# FLD_Logic_2.net
KiCad netlist of a schematic drawn in EAGLE
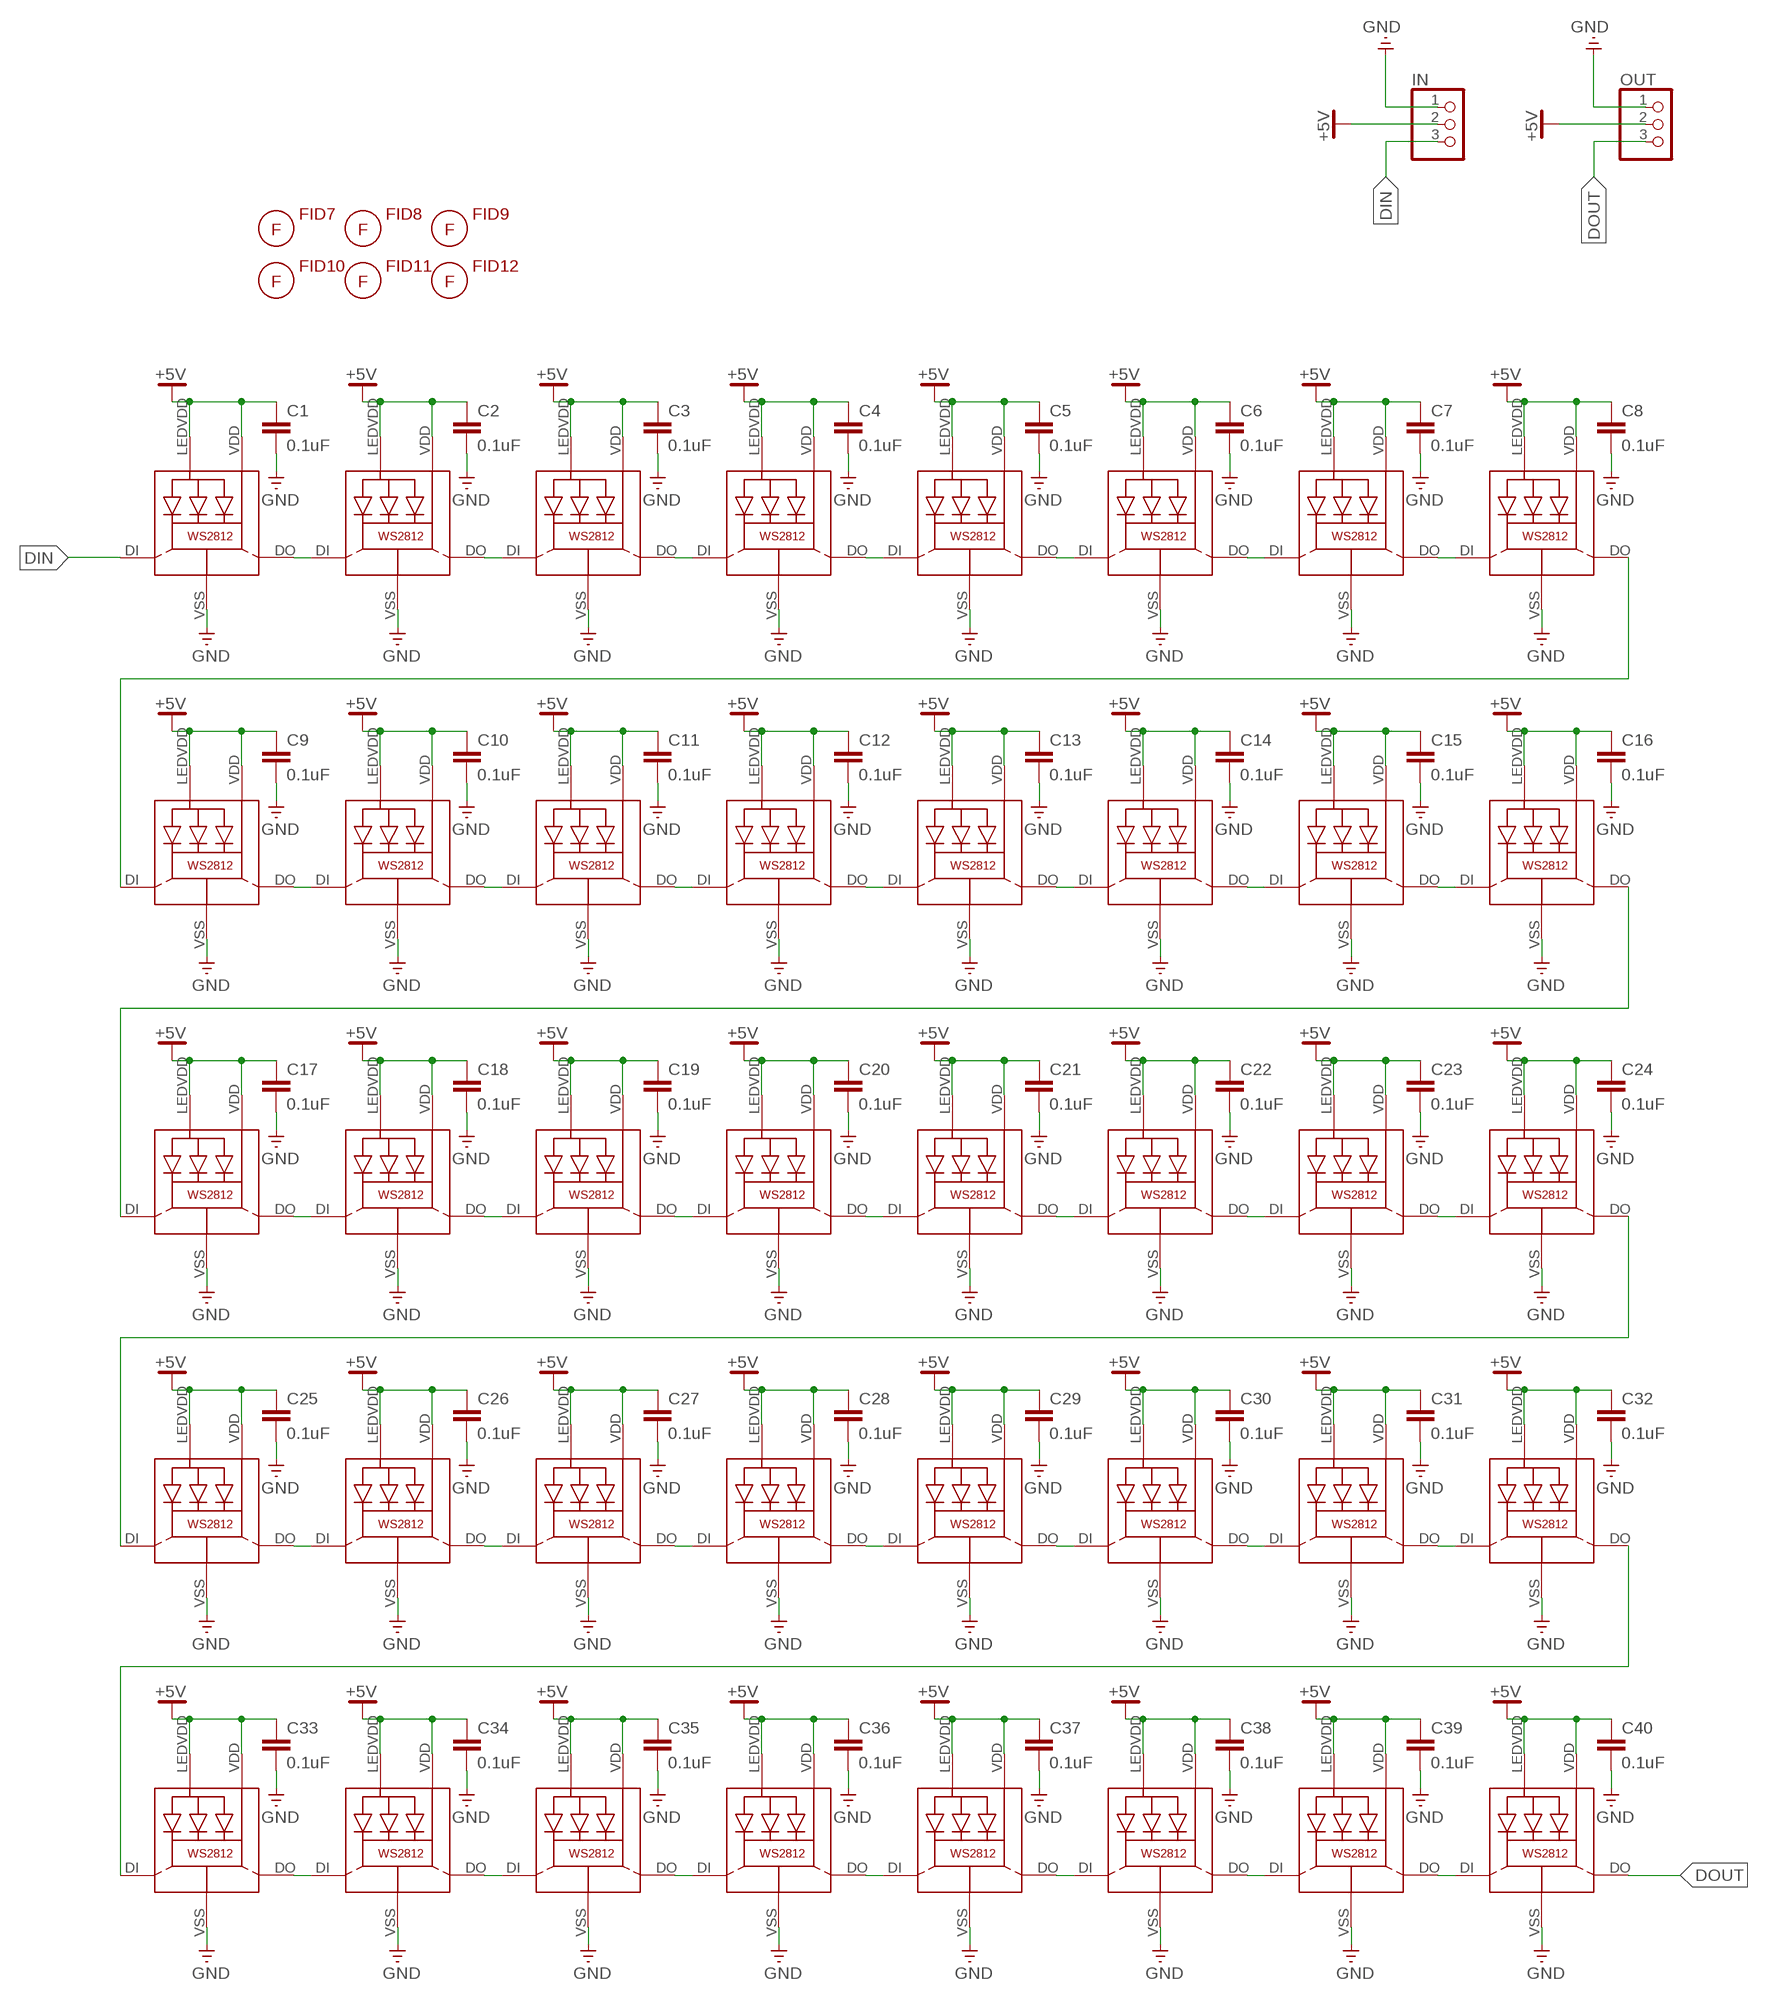
[diagram p0: schematic, sheet 1]

(export (version "E")
  (design (tool "Eeschema 10.0.6"))
  (components
    (comp (ref "C1")
      (value "0.1uF")
      (footprint "eagle-import:0805")
      (libsource (lib "eagle-import") (part "CAP0805"))
    )
    (comp (ref "C2")
      (value "0.1uF")
      (footprint "eagle-import:0805")
      (libsource (lib "eagle-import") (part "CAP0805"))
    )
    (comp (ref "C3")
      (value "0.1uF")
      (footprint "eagle-import:0805")
      (libsource (lib "eagle-import") (part "CAP0805"))
    )
    (comp (ref "C4")
      (value "0.1uF")
      (footprint "eagle-import:0805")
      (libsource (lib "eagle-import") (part "CAP0805"))
    )
    (comp (ref "C5")
      (value "0.1uF")
      (footprint "eagle-import:0805")
      (libsource (lib "eagle-import") (part "CAP0805"))
    )
    (comp (ref "C6")
      (value "0.1uF")
      (footprint "eagle-import:0805")
      (libsource (lib "eagle-import") (part "CAP0805"))
    )
    (comp (ref "C7")
      (value "0.1uF")
      (footprint "eagle-import:0805")
      (libsource (lib "eagle-import") (part "CAP0805"))
    )
    (comp (ref "C8")
      (value "0.1uF")
      (footprint "eagle-import:0805")
      (libsource (lib "eagle-import") (part "CAP0805"))
    )
    (comp (ref "C9")
      (value "0.1uF")
      (footprint "eagle-import:0805")
      (libsource (lib "eagle-import") (part "CAP0805"))
    )
    (comp (ref "C10")
      (value "0.1uF")
      (footprint "eagle-import:0805")
      (libsource (lib "eagle-import") (part "CAP0805"))
    )
    (comp (ref "C11")
      (value "0.1uF")
      (footprint "eagle-import:0805")
      (libsource (lib "eagle-import") (part "CAP0805"))
    )
    (comp (ref "C12")
      (value "0.1uF")
      (footprint "eagle-import:0805")
      (libsource (lib "eagle-import") (part "CAP0805"))
    )
    (comp (ref "C13")
      (value "0.1uF")
      (footprint "eagle-import:0805")
      (libsource (lib "eagle-import") (part "CAP0805"))
    )
    (comp (ref "C14")
      (value "0.1uF")
      (footprint "eagle-import:0805")
      (libsource (lib "eagle-import") (part "CAP0805"))
    )
    (comp (ref "C15")
      (value "0.1uF")
      (footprint "eagle-import:0805")
      (libsource (lib "eagle-import") (part "CAP0805"))
    )
    (comp (ref "C16")
      (value "0.1uF")
      (footprint "eagle-import:0805")
      (libsource (lib "eagle-import") (part "CAP0805"))
    )
    (comp (ref "C17")
      (value "0.1uF")
      (footprint "eagle-import:0805")
      (libsource (lib "eagle-import") (part "CAP0805"))
    )
    (comp (ref "C18")
      (value "0.1uF")
      (footprint "eagle-import:0805")
      (libsource (lib "eagle-import") (part "CAP0805"))
    )
    (comp (ref "C19")
      (value "0.1uF")
      (footprint "eagle-import:0805")
      (libsource (lib "eagle-import") (part "CAP0805"))
    )
    (comp (ref "C20")
      (value "0.1uF")
      (footprint "eagle-import:0805")
      (libsource (lib "eagle-import") (part "CAP0805"))
    )
    (comp (ref "C21")
      (value "0.1uF")
      (footprint "eagle-import:0805")
      (libsource (lib "eagle-import") (part "CAP0805"))
    )
    (comp (ref "C22")
      (value "0.1uF")
      (footprint "eagle-import:0805")
      (libsource (lib "eagle-import") (part "CAP0805"))
    )
    (comp (ref "C23")
      (value "0.1uF")
      (footprint "eagle-import:0805")
      (libsource (lib "eagle-import") (part "CAP0805"))
    )
    (comp (ref "C24")
      (value "0.1uF")
      (footprint "eagle-import:0805")
      (libsource (lib "eagle-import") (part "CAP0805"))
    )
    (comp (ref "C25")
      (value "0.1uF")
      (footprint "eagle-import:0805")
      (libsource (lib "eagle-import") (part "CAP0805"))
    )
    (comp (ref "C26")
      (value "0.1uF")
      (footprint "eagle-import:0805")
      (libsource (lib "eagle-import") (part "CAP0805"))
    )
    (comp (ref "C27")
      (value "0.1uF")
      (footprint "eagle-import:0805")
      (libsource (lib "eagle-import") (part "CAP0805"))
    )
    (comp (ref "C28")
      (value "0.1uF")
      (footprint "eagle-import:0805")
      (libsource (lib "eagle-import") (part "CAP0805"))
    )
    (comp (ref "C29")
      (value "0.1uF")
      (footprint "eagle-import:0805")
      (libsource (lib "eagle-import") (part "CAP0805"))
    )
    (comp (ref "C30")
      (value "0.1uF")
      (footprint "eagle-import:0805")
      (libsource (lib "eagle-import") (part "CAP0805"))
    )
    (comp (ref "C31")
      (value "0.1uF")
      (footprint "eagle-import:0805")
      (libsource (lib "eagle-import") (part "CAP0805"))
    )
    (comp (ref "C32")
      (value "0.1uF")
      (footprint "eagle-import:0805")
      (libsource (lib "eagle-import") (part "CAP0805"))
    )
    (comp (ref "C33")
      (value "0.1uF")
      (footprint "eagle-import:0805")
      (libsource (lib "eagle-import") (part "CAP0805"))
    )
    (comp (ref "C34")
      (value "0.1uF")
      (footprint "eagle-import:0805")
      (libsource (lib "eagle-import") (part "CAP0805"))
    )
    (comp (ref "C35")
      (value "0.1uF")
      (footprint "eagle-import:0805")
      (libsource (lib "eagle-import") (part "CAP0805"))
    )
    (comp (ref "C36")
      (value "0.1uF")
      (footprint "eagle-import:0805")
      (libsource (lib "eagle-import") (part "CAP0805"))
    )
    (comp (ref "C37")
      (value "0.1uF")
      (footprint "eagle-import:0805")
      (libsource (lib "eagle-import") (part "CAP0805"))
    )
    (comp (ref "C38")
      (value "0.1uF")
      (footprint "eagle-import:0805")
      (libsource (lib "eagle-import") (part "CAP0805"))
    )
    (comp (ref "C39")
      (value "0.1uF")
      (footprint "eagle-import:0805")
      (libsource (lib "eagle-import") (part "CAP0805"))
    )
    (comp (ref "C40")
      (value "0.1uF")
      (footprint "eagle-import:0805")
      (libsource (lib "eagle-import") (part "CAP0805"))
    )
    (comp (ref "FID7")
      (value "FIDUCIAL")
      (footprint "eagle-import:FIDUCIAL_G15")
      (libsource (lib "eagle-import") (part "FIDUCIAL"))
    )
    (comp (ref "FID8")
      (value "FIDUCIAL")
      (footprint "eagle-import:FIDUCIAL_G15")
      (libsource (lib "eagle-import") (part "FIDUCIAL"))
    )
    (comp (ref "FID9")
      (value "FIDUCIAL")
      (footprint "eagle-import:FIDUCIAL_G15")
      (libsource (lib "eagle-import") (part "FIDUCIAL"))
    )
    (comp (ref "FID10")
      (value "FIDUCIAL")
      (footprint "eagle-import:FIDUCIAL_G15")
      (libsource (lib "eagle-import") (part "FIDUCIAL"))
    )
    (comp (ref "FID11")
      (value "FIDUCIAL")
      (footprint "eagle-import:FIDUCIAL_G15")
      (libsource (lib "eagle-import") (part "FIDUCIAL"))
    )
    (comp (ref "FID12")
      (value "FIDUCIAL")
      (footprint "eagle-import:FIDUCIAL_G15")
      (libsource (lib "eagle-import") (part "FIDUCIAL"))
    )
    (comp (ref "IN")
      (value "PINHD-1X3")
      (footprint "eagle-import:1X03")
      (libsource (lib "eagle-import") (part "PINHD-1X3"))
    )
    (comp (ref "LED1")
      (value "WS2812")
      (footprint "eagle-import:WS2812")
      (libsource (lib "eagle-import") (part "WS2812"))
    )
    (comp (ref "LED2")
      (value "WS2812")
      (footprint "eagle-import:WS2812")
      (libsource (lib "eagle-import") (part "WS2812"))
    )
    (comp (ref "LED3")
      (value "WS2812")
      (footprint "eagle-import:WS2812")
      (libsource (lib "eagle-import") (part "WS2812"))
    )
    (comp (ref "LED4")
      (value "WS2812")
      (footprint "eagle-import:WS2812")
      (libsource (lib "eagle-import") (part "WS2812"))
    )
    (comp (ref "LED5")
      (value "WS2812")
      (footprint "eagle-import:WS2812")
      (libsource (lib "eagle-import") (part "WS2812"))
    )
    (comp (ref "LED6")
      (value "WS2812")
      (footprint "eagle-import:WS2812")
      (libsource (lib "eagle-import") (part "WS2812"))
    )
    (comp (ref "LED7")
      (value "WS2812")
      (footprint "eagle-import:WS2812")
      (libsource (lib "eagle-import") (part "WS2812"))
    )
    (comp (ref "LED8")
      (value "WS2812")
      (footprint "eagle-import:WS2812")
      (libsource (lib "eagle-import") (part "WS2812"))
    )
    (comp (ref "LED9")
      (value "WS2812")
      (footprint "eagle-import:WS2812")
      (libsource (lib "eagle-import") (part "WS2812"))
    )
    (comp (ref "LED10")
      (value "WS2812")
      (footprint "eagle-import:WS2812")
      (libsource (lib "eagle-import") (part "WS2812"))
    )
    (comp (ref "LED11")
      (value "WS2812")
      (footprint "eagle-import:WS2812")
      (libsource (lib "eagle-import") (part "WS2812"))
    )
    (comp (ref "LED12")
      (value "WS2812")
      (footprint "eagle-import:WS2812")
      (libsource (lib "eagle-import") (part "WS2812"))
    )
    (comp (ref "LED13")
      (value "WS2812")
      (footprint "eagle-import:WS2812")
      (libsource (lib "eagle-import") (part "WS2812"))
    )
    (comp (ref "LED14")
      (value "WS2812")
      (footprint "eagle-import:WS2812")
      (libsource (lib "eagle-import") (part "WS2812"))
    )
    (comp (ref "LED15")
      (value "WS2812")
      (footprint "eagle-import:WS2812")
      (libsource (lib "eagle-import") (part "WS2812"))
    )
    (comp (ref "LED16")
      (value "WS2812")
      (footprint "eagle-import:WS2812")
      (libsource (lib "eagle-import") (part "WS2812"))
    )
    (comp (ref "LED17")
      (value "WS2812")
      (footprint "eagle-import:WS2812")
      (libsource (lib "eagle-import") (part "WS2812"))
    )
    (comp (ref "LED18")
      (value "WS2812")
      (footprint "eagle-import:WS2812")
      (libsource (lib "eagle-import") (part "WS2812"))
    )
    (comp (ref "LED19")
      (value "WS2812")
      (footprint "eagle-import:WS2812")
      (libsource (lib "eagle-import") (part "WS2812"))
    )
    (comp (ref "LED20")
      (value "WS2812")
      (footprint "eagle-import:WS2812")
      (libsource (lib "eagle-import") (part "WS2812"))
    )
    (comp (ref "LED21")
      (value "WS2812")
      (footprint "eagle-import:WS2812")
      (libsource (lib "eagle-import") (part "WS2812"))
    )
    (comp (ref "LED22")
      (value "WS2812")
      (footprint "eagle-import:WS2812")
      (libsource (lib "eagle-import") (part "WS2812"))
    )
    (comp (ref "LED23")
      (value "WS2812")
      (footprint "eagle-import:WS2812")
      (libsource (lib "eagle-import") (part "WS2812"))
    )
    (comp (ref "LED24")
      (value "WS2812")
      (footprint "eagle-import:WS2812")
      (libsource (lib "eagle-import") (part "WS2812"))
    )
    (comp (ref "LED25")
      (value "WS2812")
      (footprint "eagle-import:WS2812")
      (libsource (lib "eagle-import") (part "WS2812"))
    )
    (comp (ref "LED26")
      (value "WS2812")
      (footprint "eagle-import:WS2812")
      (libsource (lib "eagle-import") (part "WS2812"))
    )
    (comp (ref "LED27")
      (value "WS2812")
      (footprint "eagle-import:WS2812")
      (libsource (lib "eagle-import") (part "WS2812"))
    )
    (comp (ref "LED28")
      (value "WS2812")
      (footprint "eagle-import:WS2812")
      (libsource (lib "eagle-import") (part "WS2812"))
    )
    (comp (ref "LED29")
      (value "WS2812")
      (footprint "eagle-import:WS2812")
      (libsource (lib "eagle-import") (part "WS2812"))
    )
    (comp (ref "LED30")
      (value "WS2812")
      (footprint "eagle-import:WS2812")
      (libsource (lib "eagle-import") (part "WS2812"))
    )
    (comp (ref "LED31")
      (value "WS2812")
      (footprint "eagle-import:WS2812")
      (libsource (lib "eagle-import") (part "WS2812"))
    )
    (comp (ref "LED32")
      (value "WS2812")
      (footprint "eagle-import:WS2812")
      (libsource (lib "eagle-import") (part "WS2812"))
    )
    (comp (ref "LED33")
      (value "WS2812")
      (footprint "eagle-import:WS2812")
      (libsource (lib "eagle-import") (part "WS2812"))
    )
    (comp (ref "LED34")
      (value "WS2812")
      (footprint "eagle-import:WS2812")
      (libsource (lib "eagle-import") (part "WS2812"))
    )
    (comp (ref "LED35")
      (value "WS2812")
      (footprint "eagle-import:WS2812")
      (libsource (lib "eagle-import") (part "WS2812"))
    )
    (comp (ref "LED36")
      (value "WS2812")
      (footprint "eagle-import:WS2812")
      (libsource (lib "eagle-import") (part "WS2812"))
    )
    (comp (ref "LED37")
      (value "WS2812")
      (footprint "eagle-import:WS2812")
      (libsource (lib "eagle-import") (part "WS2812"))
    )
    (comp (ref "LED38")
      (value "WS2812")
      (footprint "eagle-import:WS2812")
      (libsource (lib "eagle-import") (part "WS2812"))
    )
    (comp (ref "LED39")
      (value "WS2812")
      (footprint "eagle-import:WS2812")
      (libsource (lib "eagle-import") (part "WS2812"))
    )
    (comp (ref "LED40")
      (value "WS2812")
      (footprint "eagle-import:WS2812")
      (libsource (lib "eagle-import") (part "WS2812"))
    )
    (comp (ref "OUT")
      (value "PINHD-1X3")
      (footprint "eagle-import:1X03")
      (libsource (lib "eagle-import") (part "PINHD-1X3"))
    )
  )
  (nets
    (net (code "1") (name "+5V") (class "Default")
      (node (ref "C1") (pin "1") (pinfunction "1_1") (pintype "passive"))
      (node (ref "C10") (pin "1") (pinfunction "1_1") (pintype "passive"))
      (node (ref "C11") (pin "1") (pinfunction "1_1") (pintype "passive"))
      (node (ref "C12") (pin "1") (pinfunction "1_1") (pintype "passive"))
      (node (ref "C13") (pin "1") (pinfunction "1_1") (pintype "passive"))
      (node (ref "C14") (pin "1") (pinfunction "1_1") (pintype "passive"))
      (node (ref "C15") (pin "1") (pinfunction "1_1") (pintype "passive"))
      (node (ref "C16") (pin "1") (pinfunction "1_1") (pintype "passive"))
      (node (ref "C17") (pin "1") (pinfunction "1_1") (pintype "passive"))
      (node (ref "C18") (pin "1") (pinfunction "1_1") (pintype "passive"))
      (node (ref "C19") (pin "1") (pinfunction "1_1") (pintype "passive"))
      (node (ref "C2") (pin "1") (pinfunction "1_1") (pintype "passive"))
      (node (ref "C20") (pin "1") (pinfunction "1_1") (pintype "passive"))
      (node (ref "C21") (pin "1") (pinfunction "1_1") (pintype "passive"))
      (node (ref "C22") (pin "1") (pinfunction "1_1") (pintype "passive"))
      (node (ref "C23") (pin "1") (pinfunction "1_1") (pintype "passive"))
      (node (ref "C24") (pin "1") (pinfunction "1_1") (pintype "passive"))
      (node (ref "C25") (pin "1") (pinfunction "1_1") (pintype "passive"))
      (node (ref "C26") (pin "1") (pinfunction "1_1") (pintype "passive"))
      (node (ref "C27") (pin "1") (pinfunction "1_1") (pintype "passive"))
      (node (ref "C28") (pin "1") (pinfunction "1_1") (pintype "passive"))
      (node (ref "C29") (pin "1") (pinfunction "1_1") (pintype "passive"))
      (node (ref "C3") (pin "1") (pinfunction "1_1") (pintype "passive"))
      (node (ref "C30") (pin "1") (pinfunction "1_1") (pintype "passive"))
      (node (ref "C31") (pin "1") (pinfunction "1_1") (pintype "passive"))
      (node (ref "C32") (pin "1") (pinfunction "1_1") (pintype "passive"))
      (node (ref "C33") (pin "1") (pinfunction "1_1") (pintype "passive"))
      (node (ref "C34") (pin "1") (pinfunction "1_1") (pintype "passive"))
      (node (ref "C35") (pin "1") (pinfunction "1_1") (pintype "passive"))
      (node (ref "C36") (pin "1") (pinfunction "1_1") (pintype "passive"))
      (node (ref "C37") (pin "1") (pinfunction "1_1") (pintype "passive"))
      (node (ref "C38") (pin "1") (pinfunction "1_1") (pintype "passive"))
      (node (ref "C39") (pin "1") (pinfunction "1_1") (pintype "passive"))
      (node (ref "C4") (pin "1") (pinfunction "1_1") (pintype "passive"))
      (node (ref "C40") (pin "1") (pinfunction "1_1") (pintype "passive"))
      (node (ref "C5") (pin "1") (pinfunction "1_1") (pintype "passive"))
      (node (ref "C6") (pin "1") (pinfunction "1_1") (pintype "passive"))
      (node (ref "C7") (pin "1") (pinfunction "1_1") (pintype "passive"))
      (node (ref "C8") (pin "1") (pinfunction "1_1") (pintype "passive"))
      (node (ref "C9") (pin "1") (pinfunction "1_1") (pintype "passive"))
      (node (ref "IN") (pin "2") (pinfunction "2_2") (pintype "passive"))
      (node (ref "LED1") (pin "LEDVDD") (pinfunction "LEDVDD_LEDVDD") (pintype "power_in"))
      (node (ref "LED1") (pin "VDD") (pinfunction "VDD_VDD") (pintype "power_in"))
      (node (ref "LED10") (pin "LEDVDD") (pinfunction "LEDVDD_LEDVDD") (pintype "power_in"))
      (node (ref "LED10") (pin "VDD") (pinfunction "VDD_VDD") (pintype "power_in"))
      (node (ref "LED11") (pin "LEDVDD") (pinfunction "LEDVDD_LEDVDD") (pintype "power_in"))
      (node (ref "LED11") (pin "VDD") (pinfunction "VDD_VDD") (pintype "power_in"))
      (node (ref "LED12") (pin "LEDVDD") (pinfunction "LEDVDD_LEDVDD") (pintype "power_in"))
      (node (ref "LED12") (pin "VDD") (pinfunction "VDD_VDD") (pintype "power_in"))
      (node (ref "LED13") (pin "LEDVDD") (pinfunction "LEDVDD_LEDVDD") (pintype "power_in"))
      (node (ref "LED13") (pin "VDD") (pinfunction "VDD_VDD") (pintype "power_in"))
      (node (ref "LED14") (pin "LEDVDD") (pinfunction "LEDVDD_LEDVDD") (pintype "power_in"))
      (node (ref "LED14") (pin "VDD") (pinfunction "VDD_VDD") (pintype "power_in"))
      (node (ref "LED15") (pin "LEDVDD") (pinfunction "LEDVDD_LEDVDD") (pintype "power_in"))
      (node (ref "LED15") (pin "VDD") (pinfunction "VDD_VDD") (pintype "power_in"))
      (node (ref "LED16") (pin "LEDVDD") (pinfunction "LEDVDD_LEDVDD") (pintype "power_in"))
      (node (ref "LED16") (pin "VDD") (pinfunction "VDD_VDD") (pintype "power_in"))
      (node (ref "LED17") (pin "LEDVDD") (pinfunction "LEDVDD_LEDVDD") (pintype "power_in"))
      (node (ref "LED17") (pin "VDD") (pinfunction "VDD_VDD") (pintype "power_in"))
      (node (ref "LED18") (pin "LEDVDD") (pinfunction "LEDVDD_LEDVDD") (pintype "power_in"))
      (node (ref "LED18") (pin "VDD") (pinfunction "VDD_VDD") (pintype "power_in"))
      (node (ref "LED19") (pin "LEDVDD") (pinfunction "LEDVDD_LEDVDD") (pintype "power_in"))
      (node (ref "LED19") (pin "VDD") (pinfunction "VDD_VDD") (pintype "power_in"))
      (node (ref "LED2") (pin "LEDVDD") (pinfunction "LEDVDD_LEDVDD") (pintype "power_in"))
      (node (ref "LED2") (pin "VDD") (pinfunction "VDD_VDD") (pintype "power_in"))
      (node (ref "LED20") (pin "LEDVDD") (pinfunction "LEDVDD_LEDVDD") (pintype "power_in"))
      (node (ref "LED20") (pin "VDD") (pinfunction "VDD_VDD") (pintype "power_in"))
      (node (ref "LED21") (pin "LEDVDD") (pinfunction "LEDVDD_LEDVDD") (pintype "power_in"))
      (node (ref "LED21") (pin "VDD") (pinfunction "VDD_VDD") (pintype "power_in"))
      (node (ref "LED22") (pin "LEDVDD") (pinfunction "LEDVDD_LEDVDD") (pintype "power_in"))
      (node (ref "LED22") (pin "VDD") (pinfunction "VDD_VDD") (pintype "power_in"))
      (node (ref "LED23") (pin "LEDVDD") (pinfunction "LEDVDD_LEDVDD") (pintype "power_in"))
      (node (ref "LED23") (pin "VDD") (pinfunction "VDD_VDD") (pintype "power_in"))
      (node (ref "LED24") (pin "LEDVDD") (pinfunction "LEDVDD_LEDVDD") (pintype "power_in"))
      (node (ref "LED24") (pin "VDD") (pinfunction "VDD_VDD") (pintype "power_in"))
      (node (ref "LED25") (pin "LEDVDD") (pinfunction "LEDVDD_LEDVDD") (pintype "power_in"))
      (node (ref "LED25") (pin "VDD") (pinfunction "VDD_VDD") (pintype "power_in"))
      (node (ref "LED26") (pin "LEDVDD") (pinfunction "LEDVDD_LEDVDD") (pintype "power_in"))
      (node (ref "LED26") (pin "VDD") (pinfunction "VDD_VDD") (pintype "power_in"))
      (node (ref "LED27") (pin "LEDVDD") (pinfunction "LEDVDD_LEDVDD") (pintype "power_in"))
      (node (ref "LED27") (pin "VDD") (pinfunction "VDD_VDD") (pintype "power_in"))
      (node (ref "LED28") (pin "LEDVDD") (pinfunction "LEDVDD_LEDVDD") (pintype "power_in"))
      (node (ref "LED28") (pin "VDD") (pinfunction "VDD_VDD") (pintype "power_in"))
      (node (ref "LED29") (pin "LEDVDD") (pinfunction "LEDVDD_LEDVDD") (pintype "power_in"))
      (node (ref "LED29") (pin "VDD") (pinfunction "VDD_VDD") (pintype "power_in"))
      (node (ref "LED3") (pin "LEDVDD") (pinfunction "LEDVDD_LEDVDD") (pintype "power_in"))
      (node (ref "LED3") (pin "VDD") (pinfunction "VDD_VDD") (pintype "power_in"))
      (node (ref "LED30") (pin "LEDVDD") (pinfunction "LEDVDD_LEDVDD") (pintype "power_in"))
      (node (ref "LED30") (pin "VDD") (pinfunction "VDD_VDD") (pintype "power_in"))
      (node (ref "LED31") (pin "LEDVDD") (pinfunction "LEDVDD_LEDVDD") (pintype "power_in"))
      (node (ref "LED31") (pin "VDD") (pinfunction "VDD_VDD") (pintype "power_in"))
      (node (ref "LED32") (pin "LEDVDD") (pinfunction "LEDVDD_LEDVDD") (pintype "power_in"))
      (node (ref "LED32") (pin "VDD") (pinfunction "VDD_VDD") (pintype "power_in"))
      (node (ref "LED33") (pin "LEDVDD") (pinfunction "LEDVDD_LEDVDD") (pintype "power_in"))
      (node (ref "LED33") (pin "VDD") (pinfunction "VDD_VDD") (pintype "power_in"))
      (node (ref "LED34") (pin "LEDVDD") (pinfunction "LEDVDD_LEDVDD") (pintype "power_in"))
      (node (ref "LED34") (pin "VDD") (pinfunction "VDD_VDD") (pintype "power_in"))
      (node (ref "LED35") (pin "LEDVDD") (pinfunction "LEDVDD_LEDVDD") (pintype "power_in"))
      (node (ref "LED35") (pin "VDD") (pinfunction "VDD_VDD") (pintype "power_in"))
      (node (ref "LED36") (pin "LEDVDD") (pinfunction "LEDVDD_LEDVDD") (pintype "power_in"))
      (node (ref "LED36") (pin "VDD") (pinfunction "VDD_VDD") (pintype "power_in"))
      (node (ref "LED37") (pin "LEDVDD") (pinfunction "LEDVDD_LEDVDD") (pintype "power_in"))
      (node (ref "LED37") (pin "VDD") (pinfunction "VDD_VDD") (pintype "power_in"))
      (node (ref "LED38") (pin "LEDVDD") (pinfunction "LEDVDD_LEDVDD") (pintype "power_in"))
      (node (ref "LED38") (pin "VDD") (pinfunction "VDD_VDD") (pintype "power_in"))
      (node (ref "LED39") (pin "LEDVDD") (pinfunction "LEDVDD_LEDVDD") (pintype "power_in"))
      (node (ref "LED39") (pin "VDD") (pinfunction "VDD_VDD") (pintype "power_in"))
      (node (ref "LED4") (pin "LEDVDD") (pinfunction "LEDVDD_LEDVDD") (pintype "power_in"))
      (node (ref "LED4") (pin "VDD") (pinfunction "VDD_VDD") (pintype "power_in"))
      (node (ref "LED40") (pin "LEDVDD") (pinfunction "LEDVDD_LEDVDD") (pintype "power_in"))
      (node (ref "LED40") (pin "VDD") (pinfunction "VDD_VDD") (pintype "power_in"))
      (node (ref "LED5") (pin "LEDVDD") (pinfunction "LEDVDD_LEDVDD") (pintype "power_in"))
      (node (ref "LED5") (pin "VDD") (pinfunction "VDD_VDD") (pintype "power_in"))
      (node (ref "LED6") (pin "LEDVDD") (pinfunction "LEDVDD_LEDVDD") (pintype "power_in"))
      (node (ref "LED6") (pin "VDD") (pinfunction "VDD_VDD") (pintype "power_in"))
      (node (ref "LED7") (pin "LEDVDD") (pinfunction "LEDVDD_LEDVDD") (pintype "power_in"))
      (node (ref "LED7") (pin "VDD") (pinfunction "VDD_VDD") (pintype "power_in"))
      (node (ref "LED8") (pin "LEDVDD") (pinfunction "LEDVDD_LEDVDD") (pintype "power_in"))
      (node (ref "LED8") (pin "VDD") (pinfunction "VDD_VDD") (pintype "power_in"))
      (node (ref "LED9") (pin "LEDVDD") (pinfunction "LEDVDD_LEDVDD") (pintype "power_in"))
      (node (ref "LED9") (pin "VDD") (pinfunction "VDD_VDD") (pintype "power_in"))
      (node (ref "OUT") (pin "2") (pinfunction "2_2") (pintype "passive"))
    )
    (net (code "2") (name "DIN") (class "Default")
      (node (ref "IN") (pin "3") (pinfunction "3_3") (pintype "passive"))
      (node (ref "LED1") (pin "DI") (pinfunction "DI_DI") (pintype "input"))
    )
    (net (code "3") (name "DOUT") (class "Default")
      (node (ref "LED40") (pin "DO") (pinfunction "DO_DO") (pintype "output"))
      (node (ref "OUT") (pin "3") (pinfunction "3_3") (pintype "passive"))
    )
    (net (code "4") (name "GND") (class "Default")
      (node (ref "C1") (pin "2") (pinfunction "2_2") (pintype "passive"))
      (node (ref "C10") (pin "2") (pinfunction "2_2") (pintype "passive"))
      (node (ref "C11") (pin "2") (pinfunction "2_2") (pintype "passive"))
      (node (ref "C12") (pin "2") (pinfunction "2_2") (pintype "passive"))
      (node (ref "C13") (pin "2") (pinfunction "2_2") (pintype "passive"))
      (node (ref "C14") (pin "2") (pinfunction "2_2") (pintype "passive"))
      (node (ref "C15") (pin "2") (pinfunction "2_2") (pintype "passive"))
      (node (ref "C16") (pin "2") (pinfunction "2_2") (pintype "passive"))
      (node (ref "C17") (pin "2") (pinfunction "2_2") (pintype "passive"))
      (node (ref "C18") (pin "2") (pinfunction "2_2") (pintype "passive"))
      (node (ref "C19") (pin "2") (pinfunction "2_2") (pintype "passive"))
      (node (ref "C2") (pin "2") (pinfunction "2_2") (pintype "passive"))
      (node (ref "C20") (pin "2") (pinfunction "2_2") (pintype "passive"))
      (node (ref "C21") (pin "2") (pinfunction "2_2") (pintype "passive"))
      (node (ref "C22") (pin "2") (pinfunction "2_2") (pintype "passive"))
      (node (ref "C23") (pin "2") (pinfunction "2_2") (pintype "passive"))
      (node (ref "C24") (pin "2") (pinfunction "2_2") (pintype "passive"))
      (node (ref "C25") (pin "2") (pinfunction "2_2") (pintype "passive"))
      (node (ref "C26") (pin "2") (pinfunction "2_2") (pintype "passive"))
      (node (ref "C27") (pin "2") (pinfunction "2_2") (pintype "passive"))
      (node (ref "C28") (pin "2") (pinfunction "2_2") (pintype "passive"))
      (node (ref "C29") (pin "2") (pinfunction "2_2") (pintype "passive"))
      (node (ref "C3") (pin "2") (pinfunction "2_2") (pintype "passive"))
      (node (ref "C30") (pin "2") (pinfunction "2_2") (pintype "passive"))
      (node (ref "C31") (pin "2") (pinfunction "2_2") (pintype "passive"))
      (node (ref "C32") (pin "2") (pinfunction "2_2") (pintype "passive"))
      (node (ref "C33") (pin "2") (pinfunction "2_2") (pintype "passive"))
      (node (ref "C34") (pin "2") (pinfunction "2_2") (pintype "passive"))
      (node (ref "C35") (pin "2") (pinfunction "2_2") (pintype "passive"))
      (node (ref "C36") (pin "2") (pinfunction "2_2") (pintype "passive"))
      (node (ref "C37") (pin "2") (pinfunction "2_2") (pintype "passive"))
      (node (ref "C38") (pin "2") (pinfunction "2_2") (pintype "passive"))
      (node (ref "C39") (pin "2") (pinfunction "2_2") (pintype "passive"))
      (node (ref "C4") (pin "2") (pinfunction "2_2") (pintype "passive"))
      (node (ref "C40") (pin "2") (pinfunction "2_2") (pintype "passive"))
      (node (ref "C5") (pin "2") (pinfunction "2_2") (pintype "passive"))
      (node (ref "C6") (pin "2") (pinfunction "2_2") (pintype "passive"))
      (node (ref "C7") (pin "2") (pinfunction "2_2") (pintype "passive"))
      (node (ref "C8") (pin "2") (pinfunction "2_2") (pintype "passive"))
      (node (ref "C9") (pin "2") (pinfunction "2_2") (pintype "passive"))
      (node (ref "IN") (pin "1") (pinfunction "1_1") (pintype "passive"))
      (node (ref "LED1") (pin "VSS") (pinfunction "GND_VSS") (pintype "power_in"))
      (node (ref "LED10") (pin "VSS") (pinfunction "GND_VSS") (pintype "power_in"))
      (node (ref "LED11") (pin "VSS") (pinfunction "GND_VSS") (pintype "power_in"))
      (node (ref "LED12") (pin "VSS") (pinfunction "GND_VSS") (pintype "power_in"))
      (node (ref "LED13") (pin "VSS") (pinfunction "GND_VSS") (pintype "power_in"))
      (node (ref "LED14") (pin "VSS") (pinfunction "GND_VSS") (pintype "power_in"))
      (node (ref "LED15") (pin "VSS") (pinfunction "GND_VSS") (pintype "power_in"))
      (node (ref "LED16") (pin "VSS") (pinfunction "GND_VSS") (pintype "power_in"))
      (node (ref "LED17") (pin "VSS") (pinfunction "GND_VSS") (pintype "power_in"))
      (node (ref "LED18") (pin "VSS") (pinfunction "GND_VSS") (pintype "power_in"))
      (node (ref "LED19") (pin "VSS") (pinfunction "GND_VSS") (pintype "power_in"))
      (node (ref "LED2") (pin "VSS") (pinfunction "GND_VSS") (pintype "power_in"))
      (node (ref "LED20") (pin "VSS") (pinfunction "GND_VSS") (pintype "power_in"))
      (node (ref "LED21") (pin "VSS") (pinfunction "GND_VSS") (pintype "power_in"))
      (node (ref "LED22") (pin "VSS") (pinfunction "GND_VSS") (pintype "power_in"))
      (node (ref "LED23") (pin "VSS") (pinfunction "GND_VSS") (pintype "power_in"))
      (node (ref "LED24") (pin "VSS") (pinfunction "GND_VSS") (pintype "power_in"))
      (node (ref "LED25") (pin "VSS") (pinfunction "GND_VSS") (pintype "power_in"))
      (node (ref "LED26") (pin "VSS") (pinfunction "GND_VSS") (pintype "power_in"))
      (node (ref "LED27") (pin "VSS") (pinfunction "GND_VSS") (pintype "power_in"))
      (node (ref "LED28") (pin "VSS") (pinfunction "GND_VSS") (pintype "power_in"))
      (node (ref "LED29") (pin "VSS") (pinfunction "GND_VSS") (pintype "power_in"))
      (node (ref "LED3") (pin "VSS") (pinfunction "GND_VSS") (pintype "power_in"))
      (node (ref "LED30") (pin "VSS") (pinfunction "GND_VSS") (pintype "power_in"))
      (node (ref "LED31") (pin "VSS") (pinfunction "GND_VSS") (pintype "power_in"))
      (node (ref "LED32") (pin "VSS") (pinfunction "GND_VSS") (pintype "power_in"))
      (node (ref "LED33") (pin "VSS") (pinfunction "GND_VSS") (pintype "power_in"))
      (node (ref "LED34") (pin "VSS") (pinfunction "GND_VSS") (pintype "power_in"))
      (node (ref "LED35") (pin "VSS") (pinfunction "GND_VSS") (pintype "power_in"))
      (node (ref "LED36") (pin "VSS") (pinfunction "GND_VSS") (pintype "power_in"))
      (node (ref "LED37") (pin "VSS") (pinfunction "GND_VSS") (pintype "power_in"))
      (node (ref "LED38") (pin "VSS") (pinfunction "GND_VSS") (pintype "power_in"))
      (node (ref "LED39") (pin "VSS") (pinfunction "GND_VSS") (pintype "power_in"))
      (node (ref "LED4") (pin "VSS") (pinfunction "GND_VSS") (pintype "power_in"))
      (node (ref "LED40") (pin "VSS") (pinfunction "GND_VSS") (pintype "power_in"))
      (node (ref "LED5") (pin "VSS") (pinfunction "GND_VSS") (pintype "power_in"))
      (node (ref "LED6") (pin "VSS") (pinfunction "GND_VSS") (pintype "power_in"))
      (node (ref "LED7") (pin "VSS") (pinfunction "GND_VSS") (pintype "power_in"))
      (node (ref "LED8") (pin "VSS") (pinfunction "GND_VSS") (pintype "power_in"))
      (node (ref "LED9") (pin "VSS") (pinfunction "GND_VSS") (pintype "power_in"))
      (node (ref "OUT") (pin "1") (pinfunction "1_1") (pintype "passive"))
    )
    (net (code "5") (name "Net-(LED1-PadDO)") (class "Default")
      (node (ref "LED1") (pin "DO") (pinfunction "DO_DO") (pintype "output"))
      (node (ref "LED2") (pin "DI") (pinfunction "DI_DI") (pintype "input"))
    )
    (net (code "6") (name "Net-(LED2-PadDO)") (class "Default")
      (node (ref "LED2") (pin "DO") (pinfunction "DO_DO") (pintype "output"))
      (node (ref "LED3") (pin "DI") (pinfunction "DI_DI") (pintype "input"))
    )
    (net (code "7") (name "Net-(LED3-PadDO)") (class "Default")
      (node (ref "LED3") (pin "DO") (pinfunction "DO_DO") (pintype "output"))
      (node (ref "LED4") (pin "DI") (pinfunction "DI_DI") (pintype "input"))
    )
    (net (code "8") (name "Net-(LED4-PadDO)") (class "Default")
      (node (ref "LED4") (pin "DO") (pinfunction "DO_DO") (pintype "output"))
      (node (ref "LED5") (pin "DI") (pinfunction "DI_DI") (pintype "input"))
    )
    (net (code "9") (name "Net-(LED5-PadDO)") (class "Default")
      (node (ref "LED5") (pin "DO") (pinfunction "DO_DO") (pintype "output"))
      (node (ref "LED6") (pin "DI") (pinfunction "DI_DI") (pintype "input"))
    )
    (net (code "10") (name "Net-(LED6-PadDO)") (class "Default")
      (node (ref "LED6") (pin "DO") (pinfunction "DO_DO") (pintype "output"))
      (node (ref "LED7") (pin "DI") (pinfunction "DI_DI") (pintype "input"))
    )
    (net (code "11") (name "Net-(LED7-PadDO)") (class "Default")
      (node (ref "LED7") (pin "DO") (pinfunction "DO_DO") (pintype "output"))
      (node (ref "LED8") (pin "DI") (pinfunction "DI_DI") (pintype "input"))
    )
    (net (code "12") (name "Net-(LED8-PadDO)") (class "Default")
      (node (ref "LED8") (pin "DO") (pinfunction "DO_DO") (pintype "output"))
      (node (ref "LED9") (pin "DI") (pinfunction "DI_DI") (pintype "input"))
    )
    (net (code "13") (name "Net-(LED10-PadDI)") (class "Default")
      (node (ref "LED10") (pin "DI") (pinfunction "DI_DI") (pintype "input"))
      (node (ref "LED9") (pin "DO") (pinfunction "DO_DO") (pintype "output"))
    )
    (net (code "14") (name "Net-(LED10-PadDO)") (class "Default")
      (node (ref "LED10") (pin "DO") (pinfunction "DO_DO") (pintype "output"))
      (node (ref "LED11") (pin "DI") (pinfunction "DI_DI") (pintype "input"))
    )
    (net (code "15") (name "Net-(LED11-PadDO)") (class "Default")
      (node (ref "LED11") (pin "DO") (pinfunction "DO_DO") (pintype "output"))
      (node (ref "LED12") (pin "DI") (pinfunction "DI_DI") (pintype "input"))
    )
    (net (code "16") (name "Net-(LED12-PadDO)") (class "Default")
      (node (ref "LED12") (pin "DO") (pinfunction "DO_DO") (pintype "output"))
      (node (ref "LED13") (pin "DI") (pinfunction "DI_DI") (pintype "input"))
    )
    (net (code "17") (name "Net-(LED13-PadDO)") (class "Default")
      (node (ref "LED13") (pin "DO") (pinfunction "DO_DO") (pintype "output"))
      (node (ref "LED14") (pin "DI") (pinfunction "DI_DI") (pintype "input"))
    )
    (net (code "18") (name "Net-(LED14-PadDO)") (class "Default")
      (node (ref "LED14") (pin "DO") (pinfunction "DO_DO") (pintype "output"))
      (node (ref "LED15") (pin "DI") (pinfunction "DI_DI") (pintype "input"))
    )
    (net (code "19") (name "Net-(LED15-PadDO)") (class "Default")
      (node (ref "LED15") (pin "DO") (pinfunction "DO_DO") (pintype "output"))
      (node (ref "LED16") (pin "DI") (pinfunction "DI_DI") (pintype "input"))
    )
    (net (code "20") (name "Net-(LED16-PadDO)") (class "Default")
      (node (ref "LED16") (pin "DO") (pinfunction "DO_DO") (pintype "output"))
      (node (ref "LED17") (pin "DI") (pinfunction "DI_DI") (pintype "input"))
    )
    (net (code "21") (name "Net-(LED17-PadDO)") (class "Default")
      (node (ref "LED17") (pin "DO") (pinfunction "DO_DO") (pintype "output"))
      (node (ref "LED18") (pin "DI") (pinfunction "DI_DI") (pintype "input"))
    )
    (net (code "22") (name "Net-(LED18-PadDO)") (class "Default")
      (node (ref "LED18") (pin "DO") (pinfunction "DO_DO") (pintype "output"))
      (node (ref "LED19") (pin "DI") (pinfunction "DI_DI") (pintype "input"))
    )
    (net (code "23") (name "Net-(LED19-PadDO)") (class "Default")
      (node (ref "LED19") (pin "DO") (pinfunction "DO_DO") (pintype "output"))
      (node (ref "LED20") (pin "DI") (pinfunction "DI_DI") (pintype "input"))
    )
    (net (code "24") (name "Net-(LED20-PadDO)") (class "Default")
      (node (ref "LED20") (pin "DO") (pinfunction "DO_DO") (pintype "output"))
      (node (ref "LED21") (pin "DI") (pinfunction "DI_DI") (pintype "input"))
    )
    (net (code "25") (name "Net-(LED21-PadDO)") (class "Default")
      (node (ref "LED21") (pin "DO") (pinfunction "DO_DO") (pintype "output"))
      (node (ref "LED22") (pin "DI") (pinfunction "DI_DI") (pintype "input"))
    )
    (net (code "26") (name "Net-(LED22-PadDO)") (class "Default")
      (node (ref "LED22") (pin "DO") (pinfunction "DO_DO") (pintype "output"))
      (node (ref "LED23") (pin "DI") (pinfunction "DI_DI") (pintype "input"))
    )
    (net (code "27") (name "Net-(LED23-PadDO)") (class "Default")
      (node (ref "LED23") (pin "DO") (pinfunction "DO_DO") (pintype "output"))
      (node (ref "LED24") (pin "DI") (pinfunction "DI_DI") (pintype "input"))
    )
    (net (code "28") (name "Net-(LED24-PadDO)") (class "Default")
      (node (ref "LED24") (pin "DO") (pinfunction "DO_DO") (pintype "output"))
      (node (ref "LED25") (pin "DI") (pinfunction "DI_DI") (pintype "input"))
    )
    (net (code "29") (name "Net-(LED25-PadDO)") (class "Default")
      (node (ref "LED25") (pin "DO") (pinfunction "DO_DO") (pintype "output"))
      (node (ref "LED26") (pin "DI") (pinfunction "DI_DI") (pintype "input"))
    )
    (net (code "30") (name "Net-(LED26-PadDO)") (class "Default")
      (node (ref "LED26") (pin "DO") (pinfunction "DO_DO") (pintype "output"))
      (node (ref "LED27") (pin "DI") (pinfunction "DI_DI") (pintype "input"))
    )
    (net (code "31") (name "Net-(LED27-PadDO)") (class "Default")
      (node (ref "LED27") (pin "DO") (pinfunction "DO_DO") (pintype "output"))
      (node (ref "LED28") (pin "DI") (pinfunction "DI_DI") (pintype "input"))
    )
    (net (code "32") (name "Net-(LED28-PadDO)") (class "Default")
      (node (ref "LED28") (pin "DO") (pinfunction "DO_DO") (pintype "output"))
      (node (ref "LED29") (pin "DI") (pinfunction "DI_DI") (pintype "input"))
    )
    (net (code "33") (name "Net-(LED29-PadDO)") (class "Default")
      (node (ref "LED29") (pin "DO") (pinfunction "DO_DO") (pintype "output"))
      (node (ref "LED30") (pin "DI") (pinfunction "DI_DI") (pintype "input"))
    )
    (net (code "34") (name "Net-(LED30-PadDO)") (class "Default")
      (node (ref "LED30") (pin "DO") (pinfunction "DO_DO") (pintype "output"))
      (node (ref "LED31") (pin "DI") (pinfunction "DI_DI") (pintype "input"))
    )
    (net (code "35") (name "Net-(LED31-PadDO)") (class "Default")
      (node (ref "LED31") (pin "DO") (pinfunction "DO_DO") (pintype "output"))
      (node (ref "LED32") (pin "DI") (pinfunction "DI_DI") (pintype "input"))
    )
    (net (code "36") (name "Net-(LED32-PadDO)") (class "Default")
      (node (ref "LED32") (pin "DO") (pinfunction "DO_DO") (pintype "output"))
      (node (ref "LED33") (pin "DI") (pinfunction "DI_DI") (pintype "input"))
    )
    (net (code "37") (name "Net-(LED33-PadDO)") (class "Default")
      (node (ref "LED33") (pin "DO") (pinfunction "DO_DO") (pintype "output"))
      (node (ref "LED34") (pin "DI") (pinfunction "DI_DI") (pintype "input"))
    )
    (net (code "38") (name "Net-(LED34-PadDO)") (class "Default")
      (node (ref "LED34") (pin "DO") (pinfunction "DO_DO") (pintype "output"))
      (node (ref "LED35") (pin "DI") (pinfunction "DI_DI") (pintype "input"))
    )
    (net (code "39") (name "Net-(LED35-PadDO)") (class "Default")
      (node (ref "LED35") (pin "DO") (pinfunction "DO_DO") (pintype "output"))
      (node (ref "LED36") (pin "DI") (pinfunction "DI_DI") (pintype "input"))
    )
    (net (code "40") (name "Net-(LED36-PadDO)") (class "Default")
      (node (ref "LED36") (pin "DO") (pinfunction "DO_DO") (pintype "output"))
      (node (ref "LED37") (pin "DI") (pinfunction "DI_DI") (pintype "input"))
    )
    (net (code "41") (name "Net-(LED37-PadDO)") (class "Default")
      (node (ref "LED37") (pin "DO") (pinfunction "DO_DO") (pintype "output"))
      (node (ref "LED38") (pin "DI") (pinfunction "DI_DI") (pintype "input"))
    )
    (net (code "42") (name "Net-(LED38-PadDO)") (class "Default")
      (node (ref "LED38") (pin "DO") (pinfunction "DO_DO") (pintype "output"))
      (node (ref "LED39") (pin "DI") (pinfunction "DI_DI") (pintype "input"))
    )
    (net (code "43") (name "Net-(LED39-PadDO)") (class "Default")
      (node (ref "LED39") (pin "DO") (pinfunction "DO_DO") (pintype "output"))
      (node (ref "LED40") (pin "DI") (pinfunction "DI_DI") (pintype "input"))
    )
  )
)
